# pca10040_sheet5_power_supply.net
KiCad netlist of a schematic drawn in Altium Designer
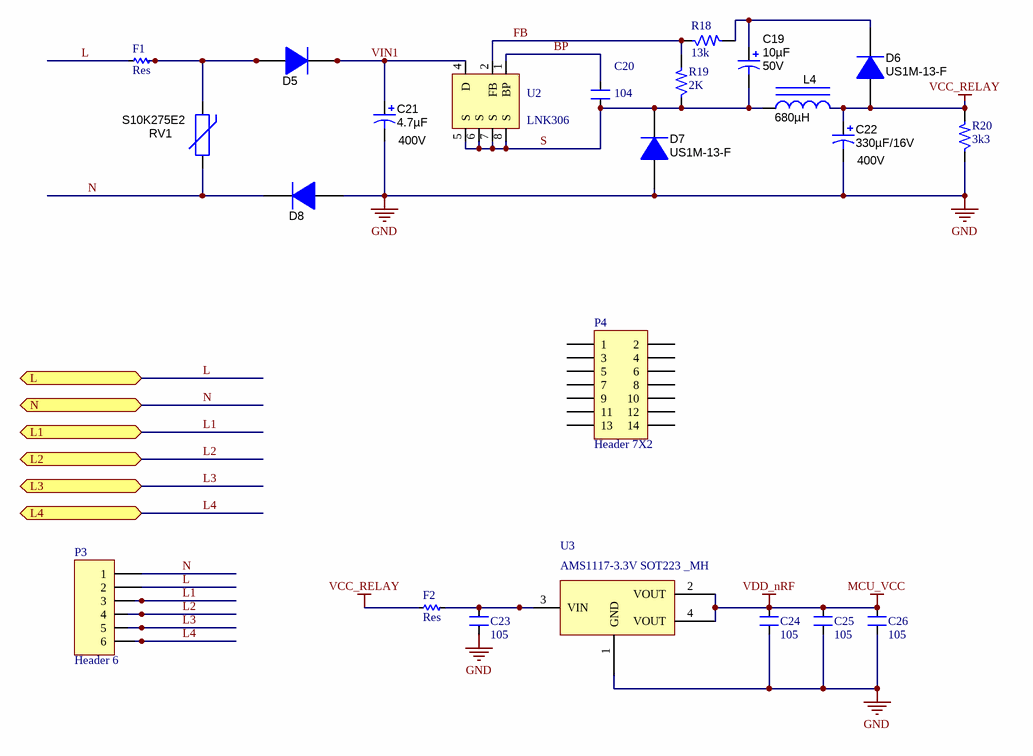
[diagram p0: pca10040_sheet5_power_supply.SchDoc]

(export (version "E")
  (design (tool "Eeschema 10.0.6"))
  (components
    (comp (ref "C19")
      (value "ECA-1HHG100")
      (footprint "PcbLib1:NHG_500x1100")
      (description "CAP, AL, 10 µF, 50 V, +/- 20%, TH")
      (fields
        (field (name "VALUEDISPLAYED") "10µF")
        (field (name "MANUFACTURER") "Panasonic")
        (field (name "VALUE2") "50V")
        (field (name "PUBLISHER") "Texas Instruments")
      )
      (libsource (lib "Capacitor_Aluminum") (part "ECA-1HHG100"))
    )
    (comp (ref "C20")
      (value "104")
      (footprint "0805_HV")
      (description "Cap SMD")
      (libsource (lib "hatcatbietbay") (part "CM"))
    )
    (comp (ref "C21")
      (value "400AX6R8M8x11")
      (footprint "PcbLib1:PANACAP-G-GENERIC")
      (description "CAP, AL, 6.8uF, 400V, +/-20%, TH")
      (fields
        (field (name "VALUEDISPLAYED") "4.7µF")
        (field (name "MANUFACTURER") "Rubycon")
        (field (name "VALUE2") "400V")
        (field (name "PUBLISHER") "Texas Instruments")
      )
      (libsource (lib "Capacitor_Aluminum") (part "400AX6R8M8x11"))
    )
    (comp (ref "C22")
      (value "400AX6R8M8x11")
      (footprint "PcbLib1:CAPPRD350W60D800H1100")
      (description "CAP, AL, 6.8uF, 400V, +/-20%, TH")
      (fields
        (field (name "VALUEDISPLAYED") "330µF/16V")
        (field (name "MANUFACTURER") "Rubycon")
        (field (name "VALUE2") "400V")
        (field (name "PUBLISHER") "Texas Instruments")
      )
      (libsource (lib "Capacitor_Aluminum") (part "400AX6R8M8x11"))
    )
    (comp (ref "C23")
      (value "105")
      (footprint "0805_HV")
      (description "Cap SMD")
      (libsource (lib "hatcatbietbay") (part "CM"))
    )
    (comp (ref "C24")
      (value "105")
      (footprint "0805_HV")
      (description "Cap SMD")
      (libsource (lib "hatcatbietbay") (part "CM"))
    )
    (comp (ref "C25")
      (value "105")
      (footprint "0805_HV")
      (description "Cap SMD")
      (libsource (lib "hatcatbietbay") (part "CM"))
    )
    (comp (ref "C26")
      (value "105")
      (footprint "0805_HV")
      (description "Cap SMD")
      (libsource (lib "hatcatbietbay") (part "CM"))
    )
    (comp (ref "D5")
      (value "US1M-13-F")
      (footprint "PcbLib1:SMB")
      (description "Diode, Ultrafast, 600V, 1A, SMB")
      (fields (field (name "MANUFACTURER") "Diodes Inc.") (field (name "PUBLISHER") "Texas Instruments"))
      (libsource (lib "Diode") (part "MURS160-13-F"))
    )
    (comp (ref "D6")
      (value "US1M-13-F")
      (footprint "PcbLib1:SMB")
      (description "Diode, Ultrafast, 600V, 1A, SMB")
      (fields
        (field (name "PARTNUMBER") "US1M-13-F")
        (field (name "MANUFACTURER") "Diodes Inc.")
        (field (name "PUBLISHER") "Texas Instruments")
      )
      (libsource (lib "Diode") (part "MURS160-13-F"))
    )
    (comp (ref "D7")
      (value "US1M-13-F")
      (footprint "PcbLib1:SMB")
      (description "Diode, Ultrafast, 600V, 1A, SMB")
      (fields
        (field (name "PARTNUMBER") "US1M-13-F")
        (field (name "MANUFACTURER") "Diodes Inc.")
        (field (name "PUBLISHER") "Texas Instruments")
      )
      (libsource (lib "Diode") (part "MURS160-13-F"))
    )
    (comp (ref "D8")
      (value "US1M-13-F")
      (footprint "PcbLib1:SMB")
      (description "Diode, Ultrafast, 600V, 1A, SMB")
      (fields (field (name "MANUFACTURER") "Diodes Inc.") (field (name "PUBLISHER") "Texas Instruments"))
      (libsource (lib "Diode") (part "MURS160-13-F"))
    )
    (comp (ref "F1")
      (value "Res")
      (footprint "1206")
      (description "Resistor")
      (fields
        (field (name "MANUFACTURER") "Generic Components")
        (field (name "PUBLISHER") "Altium Hobart Technology Centre")
      )
      (libsource (lib "LIBRARY") (part "Res-SMD"))
    )
    (comp (ref "F2")
      (value "Res")
      (footprint "1206")
      (description "Resistor")
      (fields
        (field (name "MANUFACTURER") "Generic Components")
        (field (name "PUBLISHER") "Altium Hobart Technology Centre")
      )
      (libsource (lib "LIBRARY") (part "Res-SMD"))
    )
    (comp (ref "L4")
      (value "7447480331")
      (footprint "PcbLib1:IND_WE-TI_8095")
      (description "Inductor, Wirewound, Ferrite, 330 µH, 1.4 A, 0.3 ohm, TH")
      (fields
        (field (name "VALUEDISPLAYED") "680µH")
        (field (name "MANUFACTURER") "Wurth Elektronik")
        (field (name "PUBLISHER") "Texas Instruments")
      )
      (libsource (lib "Inductor_Wurth") (part "7447480331"))
    )
    (comp (ref "P3")
      (value "Header 6")
      (footprint "CONWALL_SWITH-4")
      (description "Header, 6-Pin")
      (fields (field (name "PUBLISHER") "Altium Limited"))
      (libsource (lib "Miscellaneous Connectors") (part "Header 6"))
    )
    (comp (ref "P4")
      (value "Header 7X2")
      (footprint "CON14_1.27")
      (description "Header, 7-Pin, Dual row")
      (fields (field (name "PUBLISHER") "Altium Limited"))
      (libsource (lib "Miscellaneous Connectors") (part "Header 7X2"))
    )
    (comp (ref "R18")
      (value "13k")
      (footprint "0805_HV")
      (description "Resistor 1/4W")
      (libsource (lib "hatcatbietbay") (part "R"))
    )
    (comp (ref "R19")
      (value "2K")
      (footprint "0805_HV")
      (description "Resistor 1/4W")
      (libsource (lib "hatcatbietbay") (part "R"))
    )
    (comp (ref "R20")
      (value "3k3")
      (footprint "0805_HV")
      (description "Resistor 1/4W")
      (libsource (lib "hatcatbietbay") (part "R"))
    )
    (comp (ref "RV1")
      (value "S10K275E2")
      (footprint "PcbLib1:VAR_S10K275E2")
      (description "Varistor 275V RMS 10MM Radial, TH")
      (fields
        (field (name "MANUFACTURER") "EPCOS Inc")
        (field (name "SYMBOLCREATOR") "a0412235")
        (field (name "PUBLISHER") "Texas Instruments")
      )
      (libsource (lib "Other_Passive") (part "S10K275E2"))
    )
    (comp (ref "U2") (value "LNK306") (footprint "SOP 7") (libsource (lib "LNK304") (part "Component_1")))
    (comp (ref "U3")
      (value "AMS1117-3.3V SOT223 _MH")
      (footprint "SOT223")
      (libsource (lib "MH_DA_THU_VIEN_16122016") (part "AMS1117-3.3V SOT223 _MH"))
    )
  )
  (nets
    (net (code "1") (name "/BP") (class "Default")
      (node (ref "C20") (pin "2") (pinfunction "2_2") (pintype "passive"))
      (node (ref "U2") (pin "1") (pinfunction "BP_1") (pintype "passive"))
    )
    (net (code "2") (name "/FB") (class "Default")
      (node (ref "R18") (pin "1") (pinfunction "1_1") (pintype "passive"))
      (node (ref "R19") (pin "2") (pinfunction "2_2") (pintype "passive"))
      (node (ref "U2") (pin "2") (pinfunction "FB_2") (pintype "passive"))
    )
    (net (code "3") (name "/L") (class "Default")
      (node (ref "F1") (pin "2") (pinfunction "2_2") (pintype "passive"))
      (node (ref "P3") (pin "2") (pinfunction "2_2") (pintype "passive"))
    )
    (net (code "4") (name "/L1") (class "Default")
      (node (ref "P3") (pin "3") (pinfunction "3_3") (pintype "passive"))
    )
    (net (code "5") (name "/L2") (class "Default")
      (node (ref "P3") (pin "4") (pinfunction "4_4") (pintype "passive"))
    )
    (net (code "6") (name "/L3") (class "Default")
      (node (ref "P3") (pin "5") (pinfunction "5_5") (pintype "passive"))
    )
    (net (code "7") (name "/L4") (class "Default")
      (node (ref "P3") (pin "6") (pinfunction "6_6") (pintype "passive"))
    )
    (net (code "8") (name "/N") (class "Default")
      (node (ref "D8") (pin "1") (pinfunction "K_1") (pintype "passive"))
      (node (ref "P3") (pin "1") (pinfunction "1_1") (pintype "passive"))
      (node (ref "RV1") (pin "1") (pinfunction "1_1") (pintype "passive"))
    )
    (net (code "9") (name "/S") (class "Default")
      (node (ref "C19") (pin "2") (pinfunction "-_2") (pintype "passive"))
      (node (ref "C20") (pin "1") (pinfunction "1_1") (pintype "passive"))
      (node (ref "D7") (pin "1") (pinfunction "K_1") (pintype "passive"))
      (node (ref "L4") (pin "1") (pinfunction "1_1") (pintype "passive"))
      (node (ref "R19") (pin "1") (pinfunction "1_1") (pintype "passive"))
      (node (ref "U2") (pin "5") (pinfunction "S_5") (pintype "passive"))
      (node (ref "U2") (pin "6") (pinfunction "S_6") (pintype "passive"))
      (node (ref "U2") (pin "7") (pinfunction "S_7") (pintype "passive"))
      (node (ref "U2") (pin "8") (pinfunction "S_8") (pintype "passive"))
    )
    (net (code "10") (name "/VIN1") (class "Default")
      (node (ref "C21") (pin "1") (pinfunction "+_1") (pintype "passive"))
      (node (ref "D5") (pin "1") (pinfunction "K_1") (pintype "passive"))
      (node (ref "U2") (pin "4") (pinfunction "D_4") (pintype "passive"))
    )
    (net (code "11") (name "GND") (class "Default")
      (node (ref "C21") (pin "2") (pinfunction "-_2") (pintype "passive"))
      (node (ref "C22") (pin "2") (pinfunction "-_2") (pintype "passive"))
      (node (ref "C23") (pin "1") (pinfunction "1_1") (pintype "passive"))
      (node (ref "C24") (pin "1") (pinfunction "1_1") (pintype "passive"))
      (node (ref "C25") (pin "1") (pinfunction "1_1") (pintype "passive"))
      (node (ref "C26") (pin "1") (pinfunction "1_1") (pintype "passive"))
      (node (ref "D7") (pin "2") (pinfunction "A_2") (pintype "passive"))
      (node (ref "D8") (pin "2") (pinfunction "A_2") (pintype "passive"))
      (node (ref "R20") (pin "1") (pinfunction "1_1") (pintype "passive"))
      (node (ref "U3") (pin "1") (pinfunction "GND_1") (pintype "passive"))
    )
    (net (code "12") (name "MCU_VCC") (class "Default")
      (node (ref "C24") (pin "2") (pinfunction "2_2") (pintype "passive"))
      (node (ref "C25") (pin "2") (pinfunction "2_2") (pintype "passive"))
      (node (ref "C26") (pin "2") (pinfunction "2_2") (pintype "passive"))
      (node (ref "U3") (pin "2") (pinfunction "VOUT_2") (pintype "passive"))
      (node (ref "U3") (pin "4") (pinfunction "VOUT_4") (pintype "passive"))
    )
    (net (code "13") (name "Net-(C19-+)") (class "Default")
      (node (ref "C19") (pin "1") (pinfunction "+_1") (pintype "passive"))
      (node (ref "D6") (pin "1") (pinfunction "K_1") (pintype "passive"))
      (node (ref "R18") (pin "2") (pinfunction "2_2") (pintype "passive"))
    )
    (net (code "14") (name "Net-(D5-A)") (class "Default")
      (node (ref "D5") (pin "2") (pinfunction "A_2") (pintype "passive"))
      (node (ref "F1") (pin "1") (pinfunction "1_1") (pintype "passive"))
      (node (ref "RV1") (pin "2") (pinfunction "2_2") (pintype "passive"))
    )
    (net (code "15") (name "Net-(U3-VIN)") (class "Default")
      (node (ref "C23") (pin "2") (pinfunction "2_2") (pintype "passive"))
      (node (ref "F2") (pin "1") (pinfunction "1_1") (pintype "passive"))
      (node (ref "U3") (pin "3") (pinfunction "VIN_3") (pintype "passive"))
    )
    (net (code "16") (name "VCC_RELAY") (class "Default")
      (node (ref "C22") (pin "1") (pinfunction "+_1") (pintype "passive"))
      (node (ref "D6") (pin "2") (pinfunction "A_2") (pintype "passive"))
      (node (ref "F2") (pin "2") (pinfunction "2_2") (pintype "passive"))
      (node (ref "L4") (pin "2") (pinfunction "2_2") (pintype "passive"))
      (node (ref "R20") (pin "2") (pinfunction "2_2") (pintype "passive"))
    )
    (net (code "17") (name "unconnected-(P4-Pad1)") (class "Default")
      (node (ref "P4") (pin "1") (pinfunction "1_1") (pintype "passive"))
    )
    (net (code "18") (name "unconnected-(P4-Pad2)") (class "Default")
      (node (ref "P4") (pin "2") (pinfunction "2_2") (pintype "passive"))
    )
    (net (code "19") (name "unconnected-(P4-Pad3)") (class "Default")
      (node (ref "P4") (pin "3") (pinfunction "3_3") (pintype "passive"))
    )
    (net (code "20") (name "unconnected-(P4-Pad4)") (class "Default")
      (node (ref "P4") (pin "4") (pinfunction "4_4") (pintype "passive"))
    )
    (net (code "21") (name "unconnected-(P4-Pad5)") (class "Default")
      (node (ref "P4") (pin "5") (pinfunction "5_5") (pintype "passive"))
    )
    (net (code "22") (name "unconnected-(P4-Pad6)") (class "Default")
      (node (ref "P4") (pin "6") (pinfunction "6_6") (pintype "passive"))
    )
    (net (code "23") (name "unconnected-(P4-Pad7)") (class "Default")
      (node (ref "P4") (pin "7") (pinfunction "7_7") (pintype "passive"))
    )
    (net (code "24") (name "unconnected-(P4-Pad8)") (class "Default")
      (node (ref "P4") (pin "8") (pinfunction "8_8") (pintype "passive"))
    )
    (net (code "25") (name "unconnected-(P4-Pad9)") (class "Default")
      (node (ref "P4") (pin "9") (pinfunction "9_9") (pintype "passive"))
    )
    (net (code "26") (name "unconnected-(P4-Pad10)") (class "Default")
      (node (ref "P4") (pin "10") (pinfunction "10_10") (pintype "passive"))
    )
    (net (code "27") (name "unconnected-(P4-Pad11)") (class "Default")
      (node (ref "P4") (pin "11") (pinfunction "11_11") (pintype "passive"))
    )
    (net (code "28") (name "unconnected-(P4-Pad12)") (class "Default")
      (node (ref "P4") (pin "12") (pinfunction "12_12") (pintype "passive"))
    )
    (net (code "29") (name "unconnected-(P4-Pad13)") (class "Default")
      (node (ref "P4") (pin "13") (pinfunction "13_13") (pintype "passive"))
    )
    (net (code "30") (name "unconnected-(P4-Pad14)") (class "Default")
      (node (ref "P4") (pin "14") (pinfunction "14_14") (pintype "passive"))
    )
  )
)
